# POWER.net
KiCad netlist of a schematic drawn in Altium Designer
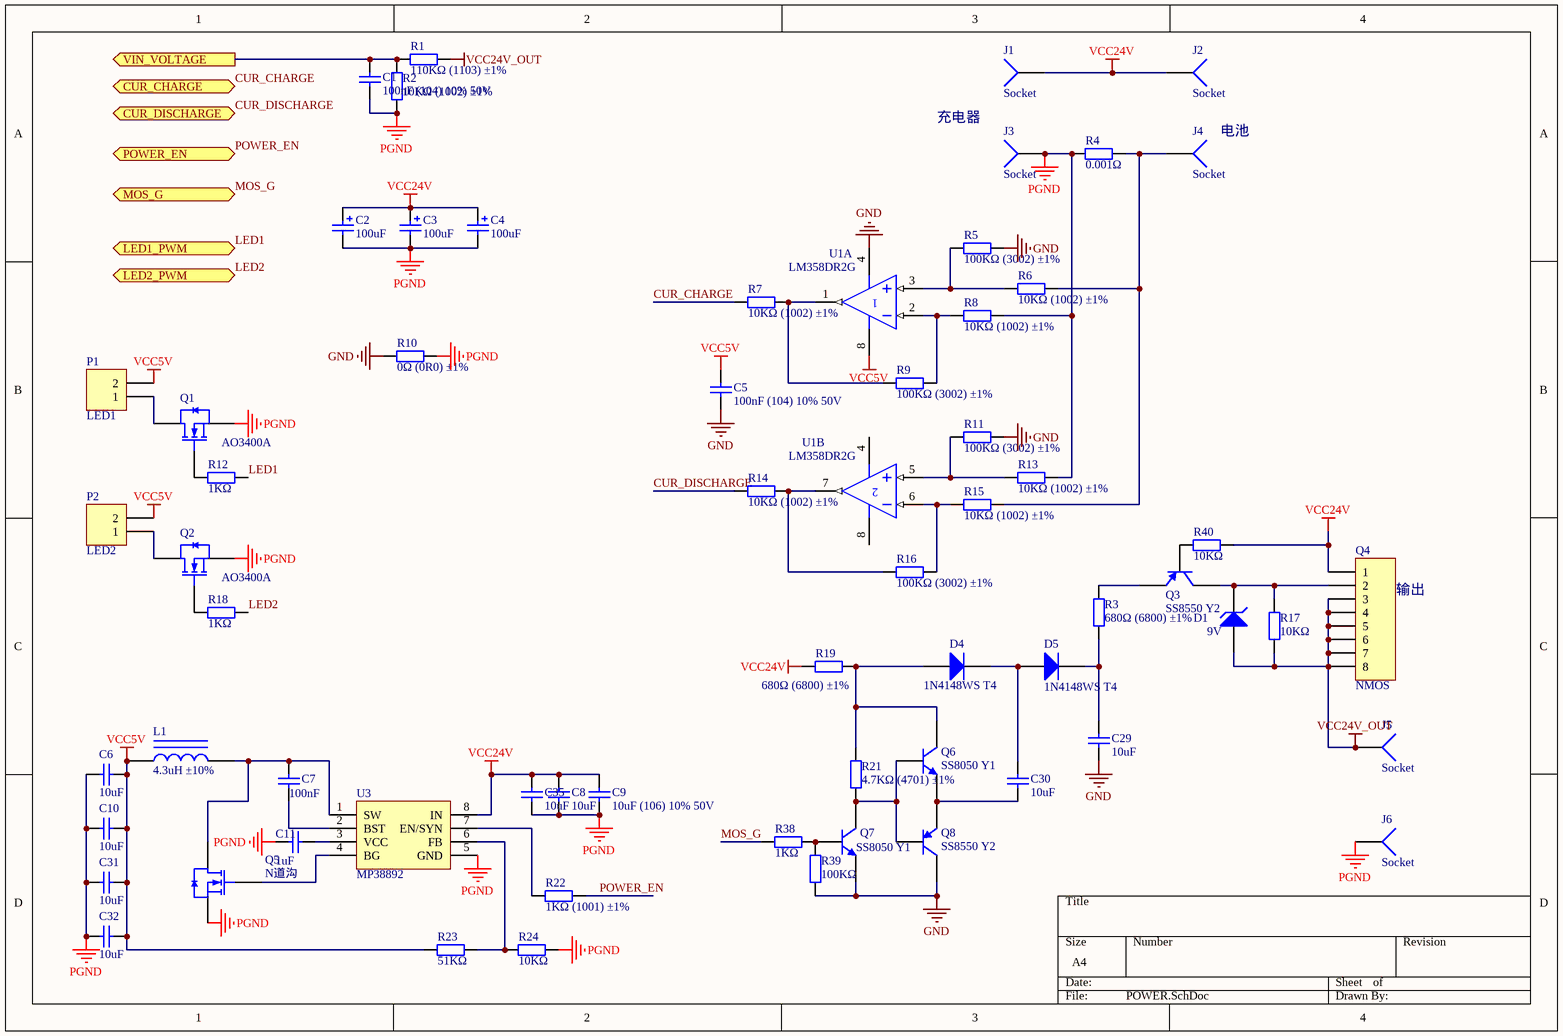
[diagram p0: POWER.SchDoc]

(export (version "E")
  (design (tool "Eeschema 10.0.6"))
  (components
    (comp (ref "C1")
      (value "100nF (104) 10% 50V")
      (footprint "0603_C")
      (description "贴片电容")
      (libsource (lib "Miscellaneous Devices LC") (part "0603 100nF (104) 10% 50V"))
    )
    (comp (ref "C2")
      (value "100uF")
      (footprint "CC6.56.5")
      (description "钽电容")
      (libsource (lib "Miscellaneous Devices LC") (part "3528 100uF (107) 10% 6.3V"))
    )
    (comp (ref "C3")
      (value "100uF")
      (footprint "CC6.56.5")
      (description "钽电容")
      (libsource (lib "Miscellaneous Devices LC") (part "3528 100uF (107) 10% 6.3V"))
    )
    (comp (ref "C4")
      (value "100uF")
      (footprint "CC6.56.5")
      (description "钽电容")
      (libsource (lib "Miscellaneous Devices LC") (part "3528 100uF (107) 10% 6.3V"))
    )
    (comp (ref "C5")
      (value "100nF (104) 10% 50V")
      (footprint "0603_C")
      (description "贴片电容")
      (libsource (lib "Miscellaneous Devices LC") (part "0603 100nF (104) 10% 50V"))
    )
    (comp (ref "C6")
      (value "10uF")
      (footprint "1206_C")
      (description "贴片电容")
      (libsource (lib "Miscellaneous Devices LC") (part "1206 10uF (106) 10% 50V"))
    )
    (comp (ref "C7")
      (value "100nF")
      (footprint "0603_C")
      (description "贴片电容")
      (libsource (lib "Miscellaneous Devices LC") (part "0603 100nF (104) 10% 50V"))
    )
    (comp (ref "C8")
      (value "10uF")
      (footprint "1206_C")
      (description "贴片电容")
      (libsource (lib "Miscellaneous Devices LC") (part "1206 10uF (106) 10% 50V"))
    )
    (comp (ref "C9")
      (value "10uF (106) 10% 50V")
      (footprint "1206_C")
      (description "贴片电容")
      (libsource (lib "Miscellaneous Devices LC") (part "1206 10uF (106) 10% 50V"))
    )
    (comp (ref "C10")
      (value "10uF")
      (footprint "1206_C")
      (description "贴片电容")
      (libsource (lib "Miscellaneous Devices LC") (part "1206 10uF (106) 10% 50V"))
    )
    (comp (ref "C11")
      (value "1uF")
      (footprint "0603_C")
      (description "贴片电容")
      (libsource (lib "Miscellaneous Devices LC") (part "0603 1uF (105) 10% 50V"))
    )
    (comp (ref "C29")
      (value "10uF")
      (footprint "0805_C")
      (description "贴片电容")
      (libsource (lib "Miscellaneous Devices LC") (part "0805 10uF (106) 10% 25V"))
    )
    (comp (ref "C30")
      (value "10uF")
      (footprint "0805_C")
      (description "贴片电容")
      (libsource (lib "Miscellaneous Devices LC") (part "0805 10uF (106) 10% 25V"))
    )
    (comp (ref "C31")
      (value "10uF")
      (footprint "1206_C")
      (description "贴片电容")
      (libsource (lib "Miscellaneous Devices LC") (part "1206 10uF (106) 10% 50V"))
    )
    (comp (ref "C32")
      (value "10uF")
      (footprint "1206_C")
      (description "贴片电容")
      (libsource (lib "Miscellaneous Devices LC") (part "1206 10uF (106) 10% 50V"))
    )
    (comp (ref "C35")
      (value "10uF")
      (footprint "1206_C")
      (description "贴片电容")
      (libsource (lib "Miscellaneous Devices LC") (part "1206 10uF (106) 10% 50V"))
    )
    (comp (ref "D1")
      (value "9V")
      (footprint "LL-34")
      (description "稳压二极管")
      (libsource (lib "Miscellaneous Devices LC") (part "LL-34 ZMM5V6"))
    )
    (comp (ref "D4")
      (value "1N4148WS T4")
      (footprint "SOD-323")
      (description "二极管")
      (libsource (lib "Miscellaneous Devices LC") (part "SOD-323 1N4148WS T4"))
    )
    (comp (ref "D5")
      (value "1N4148WS T4")
      (footprint "SOD-323")
      (description "二极管")
      (libsource (lib "Miscellaneous Devices LC") (part "SOD-323 1N4148WS T4"))
    )
    (comp (ref "J1")
      (value "Socket")
      (footprint "PIN1")
      (fields (field (name "PUBLISHER") "Altium Limited"))
      (libsource (lib "Miscellaneous Connectors") (part "Socket"))
    )
    (comp (ref "J2")
      (value "Socket")
      (footprint "PIN1")
      (fields (field (name "PUBLISHER") "Altium Limited"))
      (libsource (lib "Miscellaneous Connectors") (part "Socket"))
    )
    (comp (ref "J3")
      (value "Socket")
      (footprint "PIN1")
      (fields (field (name "PUBLISHER") "Altium Limited"))
      (libsource (lib "Miscellaneous Connectors") (part "Socket"))
    )
    (comp (ref "J4")
      (value "Socket")
      (footprint "PIN1")
      (fields (field (name "PUBLISHER") "Altium Limited"))
      (libsource (lib "Miscellaneous Connectors") (part "Socket"))
    )
    (comp (ref "J5")
      (value "Socket")
      (footprint "PIN1")
      (fields (field (name "PUBLISHER") "Altium Limited"))
      (libsource (lib "Miscellaneous Connectors") (part "Socket"))
    )
    (comp (ref "J6")
      (value "Socket")
      (footprint "PIN1")
      (fields (field (name "PUBLISHER") "Altium Limited"))
      (libsource (lib "Miscellaneous Connectors") (part "Socket"))
    )
    (comp (ref "L1")
      (value "4.3uH ±10%")
      (footprint "2225")
      (description "贴片电感")
      (libsource (lib "Miscellaneous Devices LC") (part "0805 10uH 10%"))
    )
    (comp (ref "P1")
      (value "LED1")
      (footprint "HDR1X2")
      (description "Header, 2-Pin")
      (fields (field (name "PUBLISHER") "Altium Limited"))
      (libsource (lib "Miscellaneous Connectors") (part "Header 2"))
    )
    (comp (ref "P2")
      (value "LED2")
      (footprint "HDR1X2")
      (description "Header, 2-Pin")
      (fields (field (name "PUBLISHER") "Altium Limited"))
      (libsource (lib "Miscellaneous Connectors") (part "Header 2"))
    )
    (comp (ref "Q1")
      (value "AO3400A")
      (footprint "SOT-23-3L")
      (description "MOS(场效应管)")
      (libsource (lib "Miscellaneous Devices LC") (part "AO3400A N道沟 X0YV1T SOT-23"))
    )
    (comp (ref "Q2")
      (value "AO3400A")
      (footprint "SOT-23-3L")
      (description "MOS(场效应管)")
      (libsource (lib "Miscellaneous Devices LC") (part "AO3400A N道沟 X0YV1T SOT-23"))
    )
    (comp (ref "Q3")
      (value "SS8550 Y2")
      (footprint "SOT-23(SOT-23-3)")
      (description "三极管")
      (libsource (lib "Miscellaneous Devices LC") (part "SOT-23 SS8550 Y2"))
    )
    (comp (ref "Q4")
      (value "NMOS")
      (footprint "TO-263-7")
      (description "Header, 8-Pin")
      (fields (field (name "PUBLISHER") "Altium Limited"))
      (libsource (lib "Miscellaneous Connectors") (part "Header 8"))
    )
    (comp (ref "Q5")
      (value "N道沟")
      (footprint "TO-252-2")
      (description "MOS(场效应管)")
      (libsource (lib "Miscellaneous Devices LC") (part "AO3400A N道沟 X0YV1T SOT-23"))
    )
    (comp (ref "Q6")
      (value "SS8050 Y1")
      (footprint "SOT-23(SOT-23-3)")
      (description "三极管")
      (libsource (lib "Miscellaneous Devices LC") (part "SOT-23 SS8050 Y1"))
    )
    (comp (ref "Q7")
      (value "SS8050 Y1")
      (footprint "SOT-23(SOT-23-3)")
      (description "三极管")
      (libsource (lib "Miscellaneous Devices LC") (part "SOT-23 SS8050 Y1"))
    )
    (comp (ref "Q8")
      (value "SS8550 Y2")
      (footprint "SOT-23(SOT-23-3)")
      (description "三极管")
      (libsource (lib "Miscellaneous Devices LC") (part "SOT-23 SS8550 Y2"))
    )
    (comp (ref "R1")
      (value "110KΩ (1103) ±1%")
      (footprint "0603_R")
      (description "贴片电阻")
      (libsource (lib "Miscellaneous Devices LC") (part "0603 110KΩ (1103) 1%"))
    )
    (comp (ref "R2")
      (value "10KΩ (1002) ±1%")
      (footprint "0603_R")
      (description "贴片电阻")
      (libsource (lib "") (part "0603 10KΩ (1002) 1%_1"))
    )
    (comp (ref "R3")
      (value "680Ω (6800) ±1%")
      (footprint "0603_R")
      (description "贴片电阻")
      (libsource (lib "Miscellaneous Devices LC") (part "0603 680Ω (6800) 1%"))
    )
    (comp (ref "R4")
      (value "0.001Ω")
      (footprint "2512_R")
      (description "贴片电阻")
      (libsource (lib "Miscellaneous Devices LC") (part "0603 0Ω (0R0) 1%"))
    )
    (comp (ref "R5")
      (value "100KΩ (3002) ±1%")
      (footprint "0603_R")
      (description "贴片电阻")
      (libsource (lib "") (part "0603 30KΩ (3002) 1%_1"))
    )
    (comp (ref "R6")
      (value "10KΩ (1002) ±1%")
      (footprint "0603_R")
      (description "贴片电阻")
      (libsource (lib "Miscellaneous Devices LC") (part "0603 10KΩ (1002) 1%"))
    )
    (comp (ref "R7")
      (value "10KΩ (1002) ±1%")
      (footprint "0603_R")
      (description "贴片电阻")
      (libsource (lib "Miscellaneous Devices LC") (part "0603 10KΩ (1002) 1%"))
    )
    (comp (ref "R8")
      (value "10KΩ (1002) ±1%")
      (footprint "0603_R")
      (description "贴片电阻")
      (libsource (lib "Miscellaneous Devices LC") (part "0603 10KΩ (1002) 1%"))
    )
    (comp (ref "R9")
      (value "100KΩ (3002) ±1%")
      (footprint "0603_R")
      (description "贴片电阻")
      (libsource (lib "Miscellaneous Devices LC") (part "0603 30KΩ (3002) 1%"))
    )
    (comp (ref "R10")
      (value "0Ω (0R0) ±1%")
      (footprint "0603_R")
      (description "贴片电阻")
      (libsource (lib "") (part "0603 0Ω (0R0) 1%_1"))
    )
    (comp (ref "R11")
      (value "100KΩ (3002) ±1%")
      (footprint "0603_R")
      (description "贴片电阻")
      (libsource (lib "") (part "0603 30KΩ (3002) 1%_1"))
    )
    (comp (ref "R12")
      (value "1KΩ")
      (footprint "0603_R")
      (description "贴片电阻")
      (libsource (lib "Miscellaneous Devices LC") (part "0603 1KΩ (1001) 1%"))
    )
    (comp (ref "R13")
      (value "10KΩ (1002) ±1%")
      (footprint "0603_R")
      (description "贴片电阻")
      (libsource (lib "Miscellaneous Devices LC") (part "0603 10KΩ (1002) 1%"))
    )
    (comp (ref "R14")
      (value "10KΩ (1002) ±1%")
      (footprint "0603_R")
      (description "贴片电阻")
      (libsource (lib "Miscellaneous Devices LC") (part "0603 10KΩ (1002) 1%"))
    )
    (comp (ref "R15")
      (value "10KΩ (1002) ±1%")
      (footprint "0603_R")
      (description "贴片电阻")
      (libsource (lib "Miscellaneous Devices LC") (part "0603 10KΩ (1002) 1%"))
    )
    (comp (ref "R16")
      (value "100KΩ (3002) ±1%")
      (footprint "0603_R")
      (description "贴片电阻")
      (libsource (lib "Miscellaneous Devices LC") (part "0603 30KΩ (3002) 1%"))
    )
    (comp (ref "R17")
      (value "10KΩ")
      (footprint "0603_R")
      (description "贴片电阻")
      (libsource (lib "") (part "0603 10KΩ (1002) 1%_1"))
    )
    (comp (ref "R18")
      (value "1KΩ")
      (footprint "0603_R")
      (description "贴片电阻")
      (libsource (lib "Miscellaneous Devices LC") (part "0603 1KΩ (1001) 1%"))
    )
    (comp (ref "R19")
      (value "680Ω (6800) ±1%")
      (footprint "0603_R")
      (description "贴片电阻")
      (libsource (lib "") (part "0603 680Ω (6800) 1%_1"))
    )
    (comp (ref "R21")
      (value "4.7KΩ (4701) ±1%")
      (footprint "0603_R")
      (description "贴片电阻")
      (libsource (lib "Miscellaneous Devices LC") (part "0603 4.7KΩ (4701) 1%"))
    )
    (comp (ref "R22")
      (value "1KΩ (1001) ±1%")
      (footprint "0603_R")
      (description "贴片电阻")
      (libsource (lib "") (part "0603 1KΩ (1001) 1%_1"))
    )
    (comp (ref "R23")
      (value "51KΩ")
      (footprint "0603_R")
      (description "贴片电阻")
      (libsource (lib "Miscellaneous Devices LC") (part "0603 51KΩ (5102) 1%"))
    )
    (comp (ref "R24")
      (value "10KΩ")
      (footprint "0603_R")
      (description "贴片电阻")
      (libsource (lib "") (part "0603 10KΩ (1002) 1%_2"))
    )
    (comp (ref "R38")
      (value "1KΩ")
      (footprint "0603_R")
      (description "贴片电阻")
      (libsource (lib "") (part "0603 1KΩ (1001) 1%_1"))
    )
    (comp (ref "R39")
      (value "100KΩ")
      (footprint "0603_R")
      (description "贴片电阻")
      (libsource (lib "") (part "0603 30KΩ (3002) 1%_2"))
    )
    (comp (ref "R40")
      (value "10KΩ")
      (footprint "0603_R")
      (description "贴片电阻")
      (libsource (lib "") (part "0603 10KΩ (1002) 1%_2"))
    )
    (comp (ref "U1")
      (value "LM358DR2G")
      (footprint "SOIC-8_150mil")
      (description "通用运放")
      (libsource (lib "Miscellaneous Devices LC") (part "LM358DR2G"))
    )
    (comp (ref "U3")
      (value "MP38892")
      (footprint "SOIC-8_EP_150mil")
      (libsource (lib "MySchlib") (part "MP38892"))
    )
  )
  (nets
    (net (code "1") (name "/CUR_CHARGE") (class "Default")
      (node (ref "R7") (pin "1") (pinfunction "1_1") (pintype "passive"))
    )
    (net (code "2") (name "/CUR_DISCHARGE") (class "Default")
      (node (ref "R14") (pin "1") (pinfunction "1_1") (pintype "passive"))
    )
    (net (code "3") (name "/LED1") (class "Default")
      (node (ref "R12") (pin "1") (pinfunction "1_1") (pintype "passive"))
    )
    (net (code "4") (name "/LED2") (class "Default")
      (node (ref "R18") (pin "1") (pinfunction "1_1") (pintype "passive"))
    )
    (net (code "5") (name "/MOS_G") (class "Default")
      (node (ref "R38") (pin "1") (pinfunction "1_1") (pintype "passive"))
    )
    (net (code "6") (name "/POWER_EN") (class "Default")
      (node (ref "R22") (pin "2") (pinfunction "2_2") (pintype "passive"))
    )
    (net (code "7") (name "/VIN_VOLTAGE") (class "Default")
      (node (ref "C1") (pin "1") (pinfunction "1_1") (pintype "passive"))
      (node (ref "R1") (pin "2") (pinfunction "2_2") (pintype "passive"))
      (node (ref "R2") (pin "2") (pinfunction "2_2") (pintype "passive"))
    )
    (net (code "8") (name "GND") (class "Default")
      (node (ref "C29") (pin "1") (pinfunction "1_1") (pintype "passive"))
      (node (ref "C5") (pin "2") (pinfunction "2_2") (pintype "passive"))
      (node (ref "Q7") (pin "2") (pinfunction "E_2") (pintype "passive"))
      (node (ref "Q8") (pin "3") (pinfunction "C_3") (pintype "passive"))
      (node (ref "R10") (pin "1") (pinfunction "1_1") (pintype "passive"))
      (node (ref "R11") (pin "1") (pinfunction "1_1") (pintype "passive"))
      (node (ref "R39") (pin "1") (pinfunction "1_1") (pintype "passive"))
      (node (ref "R5") (pin "1") (pinfunction "1_1") (pintype "passive"))
      (node (ref "U1") (pin "4") (pinfunction "V-_4") (pintype "power_in"))
    )
    (net (code "9") (name "Net-(D1-K)") (class "Default")
      (node (ref "D1") (pin "2") (pinfunction "K_2") (pintype "passive"))
      (node (ref "Q3") (pin "3") (pinfunction "C_3") (pintype "passive"))
      (node (ref "Q4") (pin "2") (pinfunction "2_2") (pintype "passive"))
      (node (ref "R17") (pin "2") (pinfunction "2_2") (pintype "passive"))
    )
    (net (code "10") (name "Net-(D4-A)") (class "Default")
      (node (ref "D4") (pin "1") (pinfunction "A_1") (pintype "passive"))
      (node (ref "Q6") (pin "3") (pinfunction "C_3") (pintype "passive"))
      (node (ref "R19") (pin "1") (pinfunction "1_1") (pintype "passive"))
      (node (ref "R21") (pin "2") (pinfunction "2_2") (pintype "passive"))
    )
    (net (code "11") (name "Net-(D4-K)") (class "Default")
      (node (ref "C30") (pin "2") (pinfunction "2_2") (pintype "passive"))
      (node (ref "D4") (pin "2") (pinfunction "K_2") (pintype "passive"))
      (node (ref "D5") (pin "1") (pinfunction "A_1") (pintype "passive"))
    )
    (net (code "12") (name "Net-(D5-K)") (class "Default")
      (node (ref "C29") (pin "2") (pinfunction "2_2") (pintype "passive"))
      (node (ref "D5") (pin "2") (pinfunction "K_2") (pintype "passive"))
      (node (ref "R3") (pin "2") (pinfunction "2_2") (pintype "passive"))
    )
    (net (code "13") (name "Net-(J4-Pad1)") (class "Default")
      (node (ref "J4") (pin "1") (pinfunction "1_1") (pintype "passive"))
      (node (ref "R15") (pin "2") (pinfunction "2_2") (pintype "passive"))
      (node (ref "R4") (pin "1") (pinfunction "1_1") (pintype "passive"))
      (node (ref "R6") (pin "2") (pinfunction "2_2") (pintype "passive"))
    )
    (net (code "14") (name "Net-(Q1-D)") (class "Default")
      (node (ref "P1") (pin "1") (pinfunction "1_1") (pintype "passive"))
      (node (ref "Q1") (pin "3") (pinfunction "D_3") (pintype "passive"))
    )
    (net (code "15") (name "Net-(Q1-G)") (class "Default")
      (node (ref "Q1") (pin "1") (pinfunction "G_1") (pintype "passive"))
      (node (ref "R12") (pin "2") (pinfunction "2_2") (pintype "passive"))
    )
    (net (code "16") (name "Net-(Q2-D)") (class "Default")
      (node (ref "P2") (pin "1") (pinfunction "1_1") (pintype "passive"))
      (node (ref "Q2") (pin "3") (pinfunction "D_3") (pintype "passive"))
    )
    (net (code "17") (name "Net-(Q2-G)") (class "Default")
      (node (ref "Q2") (pin "1") (pinfunction "G_1") (pintype "passive"))
      (node (ref "R18") (pin "2") (pinfunction "2_2") (pintype "passive"))
    )
    (net (code "18") (name "Net-(Q3-B)") (class "Default")
      (node (ref "Q3") (pin "1") (pinfunction "B_1") (pintype "passive"))
      (node (ref "R40") (pin "2") (pinfunction "2_2") (pintype "passive"))
    )
    (net (code "19") (name "Net-(Q3-E)") (class "Default")
      (node (ref "Q3") (pin "2") (pinfunction "E_2") (pintype "passive"))
      (node (ref "R3") (pin "1") (pinfunction "1_1") (pintype "passive"))
    )
    (net (code "20") (name "Net-(Q5-D)") (class "Default")
      (node (ref "C7") (pin "2") (pinfunction "2_2") (pintype "passive"))
      (node (ref "L1") (pin "2") (pinfunction "2_2") (pintype "passive"))
      (node (ref "Q5") (pin "3") (pinfunction "D_3") (pintype "passive"))
      (node (ref "U3") (pin "1") (pinfunction "SW_1") (pintype "passive"))
    )
    (net (code "21") (name "Net-(Q5-G)") (class "Default")
      (node (ref "Q5") (pin "1") (pinfunction "G_1") (pintype "passive"))
      (node (ref "U3") (pin "4") (pinfunction "BG_4") (pintype "passive"))
    )
    (net (code "22") (name "Net-(Q6-B)") (class "Default")
      (node (ref "Q6") (pin "1") (pinfunction "B_1") (pintype "passive"))
      (node (ref "Q7") (pin "3") (pinfunction "C_3") (pintype "passive"))
      (node (ref "Q8") (pin "1") (pinfunction "B_1") (pintype "passive"))
      (node (ref "R21") (pin "1") (pinfunction "1_1") (pintype "passive"))
    )
    (net (code "23") (name "Net-(Q6-E)") (class "Default")
      (node (ref "C30") (pin "1") (pinfunction "1_1") (pintype "passive"))
      (node (ref "Q6") (pin "2") (pinfunction "E_2") (pintype "passive"))
      (node (ref "Q8") (pin "2") (pinfunction "E_2") (pintype "passive"))
    )
    (net (code "24") (name "Net-(Q7-B)") (class "Default")
      (node (ref "Q7") (pin "1") (pinfunction "B_1") (pintype "passive"))
      (node (ref "R38") (pin "2") (pinfunction "2_2") (pintype "passive"))
      (node (ref "R39") (pin "2") (pinfunction "2_2") (pintype "passive"))
    )
    (net (code "25") (name "Net-(U1A-IN+)") (class "Default")
      (node (ref "R5") (pin "2") (pinfunction "2_2") (pintype "passive"))
      (node (ref "R6") (pin "1") (pinfunction "1_1") (pintype "passive"))
      (node (ref "U1") (pin "3") (pinfunction "IN+_3") (pintype "input"))
    )
    (net (code "26") (name "Net-(U1A-IN-)") (class "Default")
      (node (ref "R8") (pin "1") (pinfunction "1_1") (pintype "passive"))
      (node (ref "R9") (pin "2") (pinfunction "2_2") (pintype "passive"))
      (node (ref "U1") (pin "2") (pinfunction "IN-_2") (pintype "input"))
    )
    (net (code "27") (name "Net-(U1A-OUT)") (class "Default")
      (node (ref "R7") (pin "2") (pinfunction "2_2") (pintype "passive"))
      (node (ref "R9") (pin "1") (pinfunction "1_1") (pintype "passive"))
      (node (ref "U1") (pin "1") (pinfunction "OUT_1") (pintype "output"))
    )
    (net (code "28") (name "Net-(U1B-IN+)") (class "Default")
      (node (ref "R11") (pin "2") (pinfunction "2_2") (pintype "passive"))
      (node (ref "R13") (pin "1") (pinfunction "1_1") (pintype "passive"))
      (node (ref "U1") (pin "5") (pinfunction "IN+_5") (pintype "input"))
    )
    (net (code "29") (name "Net-(U1B-IN-)") (class "Default")
      (node (ref "R15") (pin "1") (pinfunction "1_1") (pintype "passive"))
      (node (ref "R16") (pin "2") (pinfunction "2_2") (pintype "passive"))
      (node (ref "U1") (pin "6") (pinfunction "IN-_6") (pintype "input"))
    )
    (net (code "30") (name "Net-(U1B-OUT)") (class "Default")
      (node (ref "R14") (pin "2") (pinfunction "2_2") (pintype "passive"))
      (node (ref "R16") (pin "1") (pinfunction "1_1") (pintype "passive"))
      (node (ref "U1") (pin "7") (pinfunction "OUT_7") (pintype "output"))
    )
    (net (code "31") (name "Net-(U3-BST)") (class "Default")
      (node (ref "C7") (pin "1") (pinfunction "1_1") (pintype "passive"))
      (node (ref "U3") (pin "2") (pinfunction "BST_2") (pintype "passive"))
    )
    (net (code "32") (name "Net-(U3-EN{slash}SYN)") (class "Default")
      (node (ref "R22") (pin "1") (pinfunction "1_1") (pintype "passive"))
      (node (ref "U3") (pin "7") (pinfunction "EN/SYN_7") (pintype "passive"))
    )
    (net (code "33") (name "Net-(U3-FB)") (class "Default")
      (node (ref "R23") (pin "1") (pinfunction "1_1") (pintype "passive"))
      (node (ref "R24") (pin "2") (pinfunction "2_2") (pintype "passive"))
      (node (ref "U3") (pin "6") (pinfunction "FB_6") (pintype "passive"))
    )
    (net (code "34") (name "Net-(U3-VCC)") (class "Default")
      (node (ref "C11") (pin "1") (pinfunction "1_1") (pintype "passive"))
      (node (ref "U3") (pin "3") (pinfunction "VCC_3") (pintype "passive"))
    )
    (net (code "35") (name "PGND") (class "Default")
      (node (ref "C1") (pin "2") (pinfunction "2_2") (pintype "passive"))
      (node (ref "C10") (pin "2") (pinfunction "2_2") (pintype "passive"))
      (node (ref "C11") (pin "2") (pinfunction "2_2") (pintype "passive"))
      (node (ref "C2") (pin "2") (pinfunction "2_2") (pintype "passive"))
      (node (ref "C3") (pin "2") (pinfunction "2_2") (pintype "passive"))
      (node (ref "C31") (pin "2") (pinfunction "2_2") (pintype "passive"))
      (node (ref "C32") (pin "2") (pinfunction "2_2") (pintype "passive"))
      (node (ref "C35") (pin "2") (pinfunction "2_2") (pintype "passive"))
      (node (ref "C4") (pin "2") (pinfunction "2_2") (pintype "passive"))
      (node (ref "C6") (pin "2") (pinfunction "2_2") (pintype "passive"))
      (node (ref "C8") (pin "1") (pinfunction "1_1") (pintype "passive"))
      (node (ref "C9") (pin "1") (pinfunction "1_1") (pintype "passive"))
      (node (ref "J3") (pin "1") (pinfunction "1_1") (pintype "passive"))
      (node (ref "J6") (pin "1") (pinfunction "1_1") (pintype "passive"))
      (node (ref "Q1") (pin "2") (pinfunction "S_2") (pintype "passive"))
      (node (ref "Q2") (pin "2") (pinfunction "S_2") (pintype "passive"))
      (node (ref "Q5") (pin "2") (pinfunction "S_2") (pintype "passive"))
      (node (ref "R10") (pin "2") (pinfunction "2_2") (pintype "passive"))
      (node (ref "R13") (pin "2") (pinfunction "2_2") (pintype "passive"))
      (node (ref "R2") (pin "1") (pinfunction "1_1") (pintype "passive"))
      (node (ref "R24") (pin "1") (pinfunction "1_1") (pintype "passive"))
      (node (ref "R4") (pin "2") (pinfunction "2_2") (pintype "passive"))
      (node (ref "R8") (pin "2") (pinfunction "2_2") (pintype "passive"))
      (node (ref "U3") (pin "5") (pinfunction "GND_5") (pintype "passive"))
    )
    (net (code "36") (name "VCC5V") (class "Default")
      (node (ref "C10") (pin "1") (pinfunction "1_1") (pintype "passive"))
      (node (ref "C31") (pin "1") (pinfunction "1_1") (pintype "passive"))
      (node (ref "C32") (pin "1") (pinfunction "1_1") (pintype "passive"))
      (node (ref "C5") (pin "1") (pinfunction "1_1") (pintype "passive"))
      (node (ref "C6") (pin "1") (pinfunction "1_1") (pintype "passive"))
      (node (ref "L1") (pin "1") (pinfunction "1_1") (pintype "passive"))
      (node (ref "P1") (pin "2") (pinfunction "2_2") (pintype "passive"))
      (node (ref "P2") (pin "2") (pinfunction "2_2") (pintype "passive"))
      (node (ref "R23") (pin "2") (pinfunction "2_2") (pintype "passive"))
      (node (ref "U1") (pin "8") (pinfunction "V+_8") (pintype "power_in"))
    )
    (net (code "37") (name "VCC24V") (class "Default")
      (node (ref "C2") (pin "1") (pinfunction "1_1") (pintype "passive"))
      (node (ref "C3") (pin "1") (pinfunction "1_1") (pintype "passive"))
      (node (ref "C35") (pin "1") (pinfunction "1_1") (pintype "passive"))
      (node (ref "C4") (pin "1") (pinfunction "1_1") (pintype "passive"))
      (node (ref "C8") (pin "2") (pinfunction "2_2") (pintype "passive"))
      (node (ref "C9") (pin "2") (pinfunction "2_2") (pintype "passive"))
      (node (ref "J1") (pin "1") (pinfunction "1_1") (pintype "passive"))
      (node (ref "J2") (pin "1") (pinfunction "1_1") (pintype "passive"))
      (node (ref "Q4") (pin "1") (pinfunction "1_1") (pintype "passive"))
      (node (ref "R19") (pin "2") (pinfunction "2_2") (pintype "passive"))
      (node (ref "R40") (pin "1") (pinfunction "1_1") (pintype "passive"))
      (node (ref "U3") (pin "8") (pinfunction "IN_8") (pintype "passive"))
    )
    (net (code "38") (name "VCC24V_OUT") (class "Default")
      (node (ref "D1") (pin "1") (pinfunction "A_1") (pintype "passive"))
      (node (ref "J5") (pin "1") (pinfunction "1_1") (pintype "passive"))
      (node (ref "Q4") (pin "3") (pinfunction "3_3") (pintype "passive"))
      (node (ref "Q4") (pin "4") (pinfunction "4_4") (pintype "passive"))
      (node (ref "Q4") (pin "5") (pinfunction "5_5") (pintype "passive"))
      (node (ref "Q4") (pin "6") (pinfunction "6_6") (pintype "passive"))
      (node (ref "Q4") (pin "7") (pinfunction "7_7") (pintype "passive"))
      (node (ref "Q4") (pin "8") (pinfunction "8_8") (pintype "passive"))
      (node (ref "R1") (pin "1") (pinfunction "1_1") (pintype "passive"))
      (node (ref "R17") (pin "1") (pinfunction "1_1") (pintype "passive"))
    )
    (net (code "39") (name "unconnected-(U1B-V+-Pad8)") (class "Default")
      (node (ref "U1") (pin "8") (pinfunction "V+_8") (pintype "power_in"))
    )
    (net (code "40") (name "unconnected-(U1B-V--Pad4)") (class "Default")
      (node (ref "U1") (pin "4") (pinfunction "V-_4") (pintype "power_in"))
    )
  )
)
